# WCH_TOUCH_Kit_EX001.net
KiCad netlist of a schematic drawn in Altium Designer
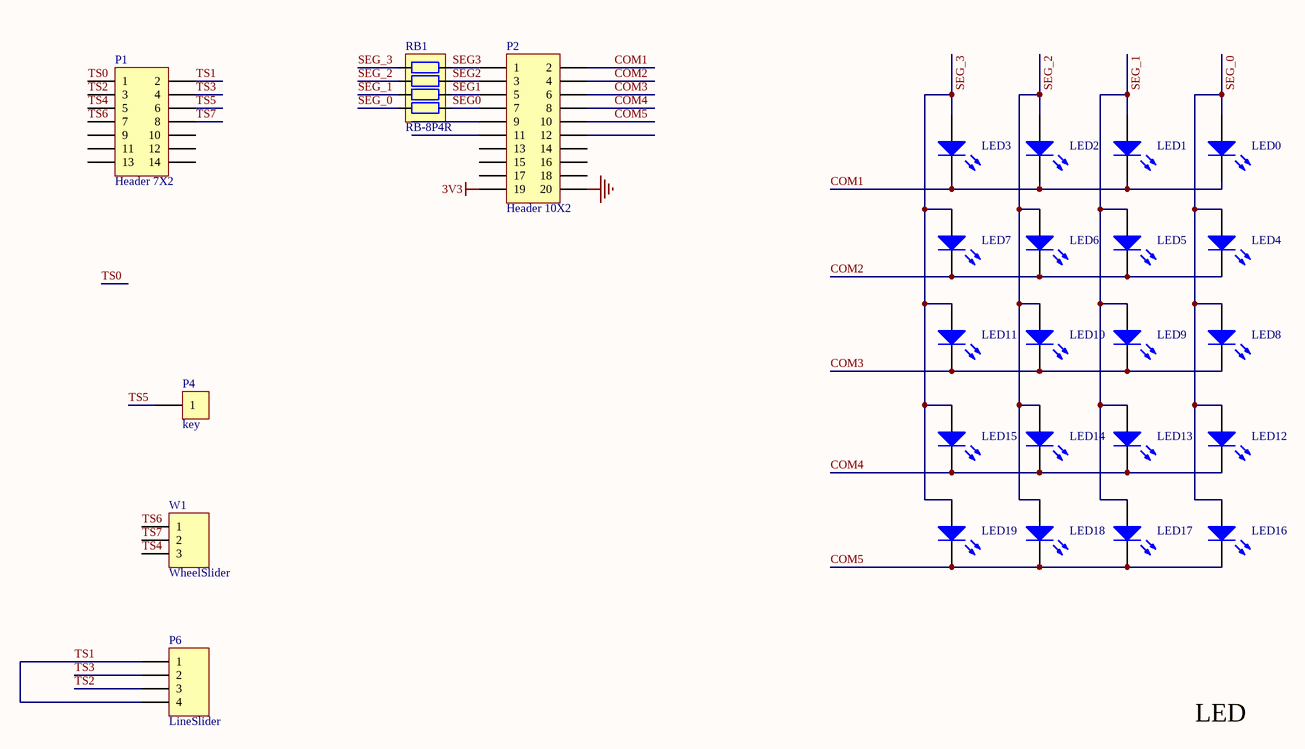
[diagram p0: WCH_TOUCH_Kit_EX001.SchDoc]

(export (version "E")
  (design (tool "Eeschema 10.0.6"))
  (components
    (comp (ref "LED0")
      (value "~")
      (footprint "LED0805-RD_EH")
      (description "Typical BLUE SiC LED")
      (fields (field (name "PUBLISHER") "Altium Limited"))
      (libsource (lib "Miscellaneous Devices") (part "LED3"))
    )
    (comp (ref "LED1")
      (value "~")
      (footprint "LED0805-RD_EH")
      (description "Typical BLUE SiC LED")
      (fields (field (name "PUBLISHER") "Altium Limited"))
      (libsource (lib "Miscellaneous Devices") (part "LED3"))
    )
    (comp (ref "LED2")
      (value "~")
      (footprint "LED0805-RD_EH")
      (description "Typical BLUE SiC LED")
      (fields (field (name "PUBLISHER") "Altium Limited"))
      (libsource (lib "Miscellaneous Devices") (part "LED3"))
    )
    (comp (ref "LED3")
      (value "~")
      (footprint "LED0805-RD_EH")
      (description "Typical BLUE SiC LED")
      (fields (field (name "PUBLISHER") "Altium Limited"))
      (libsource (lib "Miscellaneous Devices") (part "LED3"))
    )
    (comp (ref "LED4")
      (value "~")
      (footprint "LED0805-RD_EH")
      (description "Typical BLUE SiC LED")
      (fields (field (name "PUBLISHER") "Altium Limited"))
      (libsource (lib "Miscellaneous Devices") (part "LED3"))
    )
    (comp (ref "LED5")
      (value "~")
      (footprint "LED0805-RD_EH")
      (description "Typical BLUE SiC LED")
      (fields (field (name "PUBLISHER") "Altium Limited"))
      (libsource (lib "Miscellaneous Devices") (part "LED3"))
    )
    (comp (ref "LED6")
      (value "~")
      (footprint "LED0805-RD_EH")
      (description "Typical BLUE SiC LED")
      (fields (field (name "PUBLISHER") "Altium Limited"))
      (libsource (lib "Miscellaneous Devices") (part "LED3"))
    )
    (comp (ref "LED7")
      (value "~")
      (footprint "LED0805-RD_EH")
      (description "Typical BLUE SiC LED")
      (fields (field (name "PUBLISHER") "Altium Limited"))
      (libsource (lib "Miscellaneous Devices") (part "LED3"))
    )
    (comp (ref "LED8")
      (value "~")
      (footprint "LED0805-RD_EH")
      (description "Typical BLUE SiC LED")
      (fields (field (name "PUBLISHER") "Altium Limited"))
      (libsource (lib "Miscellaneous Devices") (part "LED3"))
    )
    (comp (ref "LED9")
      (value "~")
      (footprint "LED0805-RD_EH")
      (description "Typical BLUE SiC LED")
      (fields (field (name "PUBLISHER") "Altium Limited"))
      (libsource (lib "Miscellaneous Devices") (part "LED3"))
    )
    (comp (ref "LED10")
      (value "~")
      (footprint "LED0805-RD_EH")
      (description "Typical BLUE SiC LED")
      (fields (field (name "PUBLISHER") "Altium Limited"))
      (libsource (lib "Miscellaneous Devices") (part "LED3"))
    )
    (comp (ref "LED11")
      (value "~")
      (footprint "LED0805-RD_EH")
      (description "Typical BLUE SiC LED")
      (fields (field (name "PUBLISHER") "Altium Limited"))
      (libsource (lib "Miscellaneous Devices") (part "LED3"))
    )
    (comp (ref "LED12")
      (value "~")
      (footprint "LED0805-RD_EH")
      (description "Typical BLUE SiC LED")
      (fields (field (name "PUBLISHER") "Altium Limited"))
      (libsource (lib "Miscellaneous Devices") (part "LED3"))
    )
    (comp (ref "LED13")
      (value "~")
      (footprint "LED0805-RD_EH")
      (description "Typical BLUE SiC LED")
      (fields (field (name "PUBLISHER") "Altium Limited"))
      (libsource (lib "Miscellaneous Devices") (part "LED3"))
    )
    (comp (ref "LED14")
      (value "~")
      (footprint "LED0805-RD_EH")
      (description "Typical BLUE SiC LED")
      (fields (field (name "PUBLISHER") "Altium Limited"))
      (libsource (lib "Miscellaneous Devices") (part "LED3"))
    )
    (comp (ref "LED15")
      (value "~")
      (footprint "LED0805-RD_EH")
      (description "Typical BLUE SiC LED")
      (fields (field (name "PUBLISHER") "Altium Limited"))
      (libsource (lib "Miscellaneous Devices") (part "LED3"))
    )
    (comp (ref "LED16")
      (value "~")
      (footprint "LED0805-RD_EH")
      (description "Typical BLUE SiC LED")
      (fields (field (name "PUBLISHER") "Altium Limited"))
      (libsource (lib "Miscellaneous Devices") (part "LED3"))
    )
    (comp (ref "LED17")
      (value "~")
      (footprint "LED0805-RD_EH")
      (description "Typical BLUE SiC LED")
      (fields (field (name "PUBLISHER") "Altium Limited"))
      (libsource (lib "Miscellaneous Devices") (part "LED3"))
    )
    (comp (ref "LED18")
      (value "~")
      (footprint "LED0805-RD_EH")
      (description "Typical BLUE SiC LED")
      (fields (field (name "PUBLISHER") "Altium Limited"))
      (libsource (lib "Miscellaneous Devices") (part "LED3"))
    )
    (comp (ref "LED19")
      (value "~")
      (footprint "LED0805-RD_EH")
      (description "Typical BLUE SiC LED")
      (fields (field (name "PUBLISHER") "Altium Limited"))
      (libsource (lib "Miscellaneous Devices") (part "LED3"))
    )
    (comp (ref "P1")
      (value "Header 7X2")
      (footprint "HDR-TH_14P-P2.54-H-F-R2-C10-W8.5")
      (description "Header, 7-Pin, Dual row")
      (fields (field (name "PUBLISHER") "Altium Limited"))
      (libsource (lib "Miscellaneous Connectors") (part "Header 7X2"))
    )
    (comp (ref "P2")
      (value "Header 10X2")
      (footprint "HDR-TH_20P-P2.54-H-F-R2-C10-W8.5")
      (description "Header, 10-Pin, Dual row")
      (fields (field (name "PUBLISHER") "Altium Limited"))
      (libsource (lib "Miscellaneous Connectors") (part "Header 10X2"))
    )
    (comp (ref "P4")
      (value "key")
      (footprint "MYPCB:key")
      (description "Header, 1-Pin")
      (libsource (lib "wch_sch_others") (part "HEADER 1"))
    )
    (comp (ref "P6")
      (value "LineSlider")
      (footprint "Slider_4_46X8.5")
      (description "Header, 4-Pin")
      (libsource (lib "wch_sch_others") (part "HEADER 4"))
    )
    (comp (ref "RB1")
      (value "RB-8P4R")
      (footprint "RCA-8P4R-0603")
      (description "贴片网络排阻")
      (libsource (lib "wch_sch_others") (part "RB-8P4R"))
    )
    (comp (ref "W1")
      (value "WheelSlider")
      (footprint "滑轮10-18-3")
      (description "Header, 3-Pin")
      (libsource (lib "wch_sch_others") (part "HEADER 3"))
    )
  )
  (nets
    (net (code "1") (name "/COM1") (class "Default")
      (node (ref "LED0") (pin "2") (pinfunction "K_2") (pintype "passive"))
      (node (ref "LED1") (pin "2") (pinfunction "K_2") (pintype "passive"))
      (node (ref "LED2") (pin "2") (pinfunction "K_2") (pintype "passive"))
      (node (ref "LED3") (pin "2") (pinfunction "K_2") (pintype "passive"))
      (node (ref "P2") (pin "2") (pinfunction "2_2") (pintype "passive"))
    )
    (net (code "2") (name "/COM2") (class "Default")
      (node (ref "LED4") (pin "2") (pinfunction "K_2") (pintype "passive"))
      (node (ref "LED5") (pin "2") (pinfunction "K_2") (pintype "passive"))
      (node (ref "LED6") (pin "2") (pinfunction "K_2") (pintype "passive"))
      (node (ref "LED7") (pin "2") (pinfunction "K_2") (pintype "passive"))
      (node (ref "P2") (pin "4") (pinfunction "4_4") (pintype "passive"))
    )
    (net (code "3") (name "/COM3") (class "Default")
      (node (ref "LED10") (pin "2") (pinfunction "K_2") (pintype "passive"))
      (node (ref "LED11") (pin "2") (pinfunction "K_2") (pintype "passive"))
      (node (ref "LED8") (pin "2") (pinfunction "K_2") (pintype "passive"))
      (node (ref "LED9") (pin "2") (pinfunction "K_2") (pintype "passive"))
      (node (ref "P2") (pin "6") (pinfunction "6_6") (pintype "passive"))
    )
    (net (code "4") (name "/COM4") (class "Default")
      (node (ref "LED12") (pin "2") (pinfunction "K_2") (pintype "passive"))
      (node (ref "LED13") (pin "2") (pinfunction "K_2") (pintype "passive"))
      (node (ref "LED14") (pin "2") (pinfunction "K_2") (pintype "passive"))
      (node (ref "LED15") (pin "2") (pinfunction "K_2") (pintype "passive"))
      (node (ref "P2") (pin "8") (pinfunction "8_8") (pintype "passive"))
    )
    (net (code "5") (name "/COM5") (class "Default")
      (node (ref "LED16") (pin "2") (pinfunction "K_2") (pintype "passive"))
      (node (ref "LED17") (pin "2") (pinfunction "K_2") (pintype "passive"))
      (node (ref "LED18") (pin "2") (pinfunction "K_2") (pintype "passive"))
      (node (ref "LED19") (pin "2") (pinfunction "K_2") (pintype "passive"))
      (node (ref "P2") (pin "10") (pinfunction "10_10") (pintype "passive"))
    )
    (net (code "6") (name "/SEG0") (class "Default")
      (node (ref "P2") (pin "7") (pinfunction "7_7") (pintype "passive"))
      (node (ref "RB1") (pin "4") (pinfunction "4_4") (pintype "passive"))
    )
    (net (code "7") (name "/SEG1") (class "Default")
      (node (ref "P2") (pin "5") (pinfunction "5_5") (pintype "passive"))
      (node (ref "RB1") (pin "3") (pinfunction "3_3") (pintype "passive"))
    )
    (net (code "8") (name "/SEG2") (class "Default")
      (node (ref "P2") (pin "3") (pinfunction "3_3") (pintype "passive"))
      (node (ref "RB1") (pin "2") (pinfunction "2_2") (pintype "passive"))
    )
    (net (code "9") (name "/SEG3") (class "Default")
      (node (ref "P2") (pin "1") (pinfunction "1_1") (pintype "passive"))
      (node (ref "RB1") (pin "1") (pinfunction "1_1") (pintype "passive"))
    )
    (net (code "10") (name "/SEG_0") (class "Default")
      (node (ref "LED0") (pin "1") (pinfunction "A_1") (pintype "passive"))
      (node (ref "LED12") (pin "1") (pinfunction "A_1") (pintype "passive"))
      (node (ref "LED16") (pin "1") (pinfunction "A_1") (pintype "passive"))
      (node (ref "LED4") (pin "1") (pinfunction "A_1") (pintype "passive"))
      (node (ref "LED8") (pin "1") (pinfunction "A_1") (pintype "passive"))
      (node (ref "RB1") (pin "5") (pinfunction "5_5") (pintype "passive"))
    )
    (net (code "11") (name "/SEG_1") (class "Default")
      (node (ref "LED1") (pin "1") (pinfunction "A_1") (pintype "passive"))
      (node (ref "LED13") (pin "1") (pinfunction "A_1") (pintype "passive"))
      (node (ref "LED17") (pin "1") (pinfunction "A_1") (pintype "passive"))
      (node (ref "LED5") (pin "1") (pinfunction "A_1") (pintype "passive"))
      (node (ref "LED9") (pin "1") (pinfunction "A_1") (pintype "passive"))
      (node (ref "RB1") (pin "6") (pinfunction "6_6") (pintype "passive"))
    )
    (net (code "12") (name "/SEG_2") (class "Default")
      (node (ref "LED10") (pin "1") (pinfunction "A_1") (pintype "passive"))
      (node (ref "LED14") (pin "1") (pinfunction "A_1") (pintype "passive"))
      (node (ref "LED18") (pin "1") (pinfunction "A_1") (pintype "passive"))
      (node (ref "LED2") (pin "1") (pinfunction "A_1") (pintype "passive"))
      (node (ref "LED6") (pin "1") (pinfunction "A_1") (pintype "passive"))
      (node (ref "RB1") (pin "7") (pinfunction "7_7") (pintype "passive"))
    )
    (net (code "13") (name "/SEG_3") (class "Default")
      (node (ref "LED11") (pin "1") (pinfunction "A_1") (pintype "passive"))
      (node (ref "LED15") (pin "1") (pinfunction "A_1") (pintype "passive"))
      (node (ref "LED19") (pin "1") (pinfunction "A_1") (pintype "passive"))
      (node (ref "LED3") (pin "1") (pinfunction "A_1") (pintype "passive"))
      (node (ref "LED7") (pin "1") (pinfunction "A_1") (pintype "passive"))
      (node (ref "RB1") (pin "8") (pinfunction "8_8") (pintype "passive"))
    )
    (net (code "14") (name "/TS0") (class "Default")
      (node (ref "P1") (pin "1") (pinfunction "1_1") (pintype "passive"))
    )
    (net (code "15") (name "/TS1") (class "Default")
      (node (ref "P1") (pin "2") (pinfunction "2_2") (pintype "passive"))
      (node (ref "P6") (pin "1") (pinfunction "1_1") (pintype "passive"))
      (node (ref "P6") (pin "4") (pinfunction "4_4") (pintype "passive"))
    )
    (net (code "16") (name "/TS2") (class "Default")
      (node (ref "P1") (pin "3") (pinfunction "3_3") (pintype "passive"))
      (node (ref "P6") (pin "3") (pinfunction "3_3") (pintype "passive"))
    )
    (net (code "17") (name "/TS3") (class "Default")
      (node (ref "P1") (pin "4") (pinfunction "4_4") (pintype "passive"))
      (node (ref "P6") (pin "2") (pinfunction "2_2") (pintype "passive"))
    )
    (net (code "18") (name "/TS4") (class "Default")
      (node (ref "P1") (pin "5") (pinfunction "5_5") (pintype "passive"))
      (node (ref "W1") (pin "3") (pinfunction "3_3") (pintype "passive"))
    )
    (net (code "19") (name "/TS5") (class "Default")
      (node (ref "P1") (pin "6") (pinfunction "6_6") (pintype "passive"))
      (node (ref "P4") (pin "1") (pinfunction "1_1") (pintype "passive"))
    )
    (net (code "20") (name "/TS6") (class "Default")
      (node (ref "P1") (pin "7") (pinfunction "7_7") (pintype "passive"))
      (node (ref "W1") (pin "1") (pinfunction "1_1") (pintype "passive"))
    )
    (net (code "21") (name "/TS7") (class "Default")
      (node (ref "P1") (pin "8") (pinfunction "8_8") (pintype "passive"))
      (node (ref "W1") (pin "2") (pinfunction "2_2") (pintype "passive"))
    )
    (net (code "22") (name "3V3") (class "Default")
      (node (ref "P2") (pin "19") (pinfunction "19_19") (pintype "passive"))
    )
    (net (code "23") (name "GND") (class "Default")
      (node (ref "P2") (pin "20") (pinfunction "20_20") (pintype "passive"))
    )
    (net (code "24") (name "unconnected-(P1-Pad9)") (class "Default")
      (node (ref "P1") (pin "9") (pinfunction "9_9") (pintype "passive"))
    )
    (net (code "25") (name "unconnected-(P1-Pad10)") (class "Default")
      (node (ref "P1") (pin "10") (pinfunction "10_10") (pintype "passive"))
    )
    (net (code "26") (name "unconnected-(P1-Pad11)") (class "Default")
      (node (ref "P1") (pin "11") (pinfunction "11_11") (pintype "passive"))
    )
    (net (code "27") (name "unconnected-(P1-Pad12)") (class "Default")
      (node (ref "P1") (pin "12") (pinfunction "12_12") (pintype "passive"))
    )
    (net (code "28") (name "unconnected-(P1-Pad13)") (class "Default")
      (node (ref "P1") (pin "13") (pinfunction "13_13") (pintype "passive"))
    )
    (net (code "29") (name "unconnected-(P1-Pad14)") (class "Default")
      (node (ref "P1") (pin "14") (pinfunction "14_14") (pintype "passive"))
    )
    (net (code "30") (name "unconnected-(P2-Pad9)") (class "Default")
      (node (ref "P2") (pin "9") (pinfunction "9_9") (pintype "passive"))
    )
    (net (code "31") (name "unconnected-(P2-Pad11)") (class "Default")
      (node (ref "P2") (pin "11") (pinfunction "11_11") (pintype "passive"))
    )
    (net (code "32") (name "unconnected-(P2-Pad12)") (class "Default")
      (node (ref "P2") (pin "12") (pinfunction "12_12") (pintype "passive"))
    )
    (net (code "33") (name "unconnected-(P2-Pad13)") (class "Default")
      (node (ref "P2") (pin "13") (pinfunction "13_13") (pintype "passive"))
    )
    (net (code "34") (name "unconnected-(P2-Pad14)") (class "Default")
      (node (ref "P2") (pin "14") (pinfunction "14_14") (pintype "passive"))
    )
    (net (code "35") (name "unconnected-(P2-Pad15)") (class "Default")
      (node (ref "P2") (pin "15") (pinfunction "15_15") (pintype "passive"))
    )
    (net (code "36") (name "unconnected-(P2-Pad16)") (class "Default")
      (node (ref "P2") (pin "16") (pinfunction "16_16") (pintype "passive"))
    )
    (net (code "37") (name "unconnected-(P2-Pad17)") (class "Default")
      (node (ref "P2") (pin "17") (pinfunction "17_17") (pintype "passive"))
    )
    (net (code "38") (name "unconnected-(P2-Pad18)") (class "Default")
      (node (ref "P2") (pin "18") (pinfunction "18_18") (pintype "passive"))
    )
  )
)
